# Surf5.net
KiCad netlist of a schematic drawn in Altium Designer
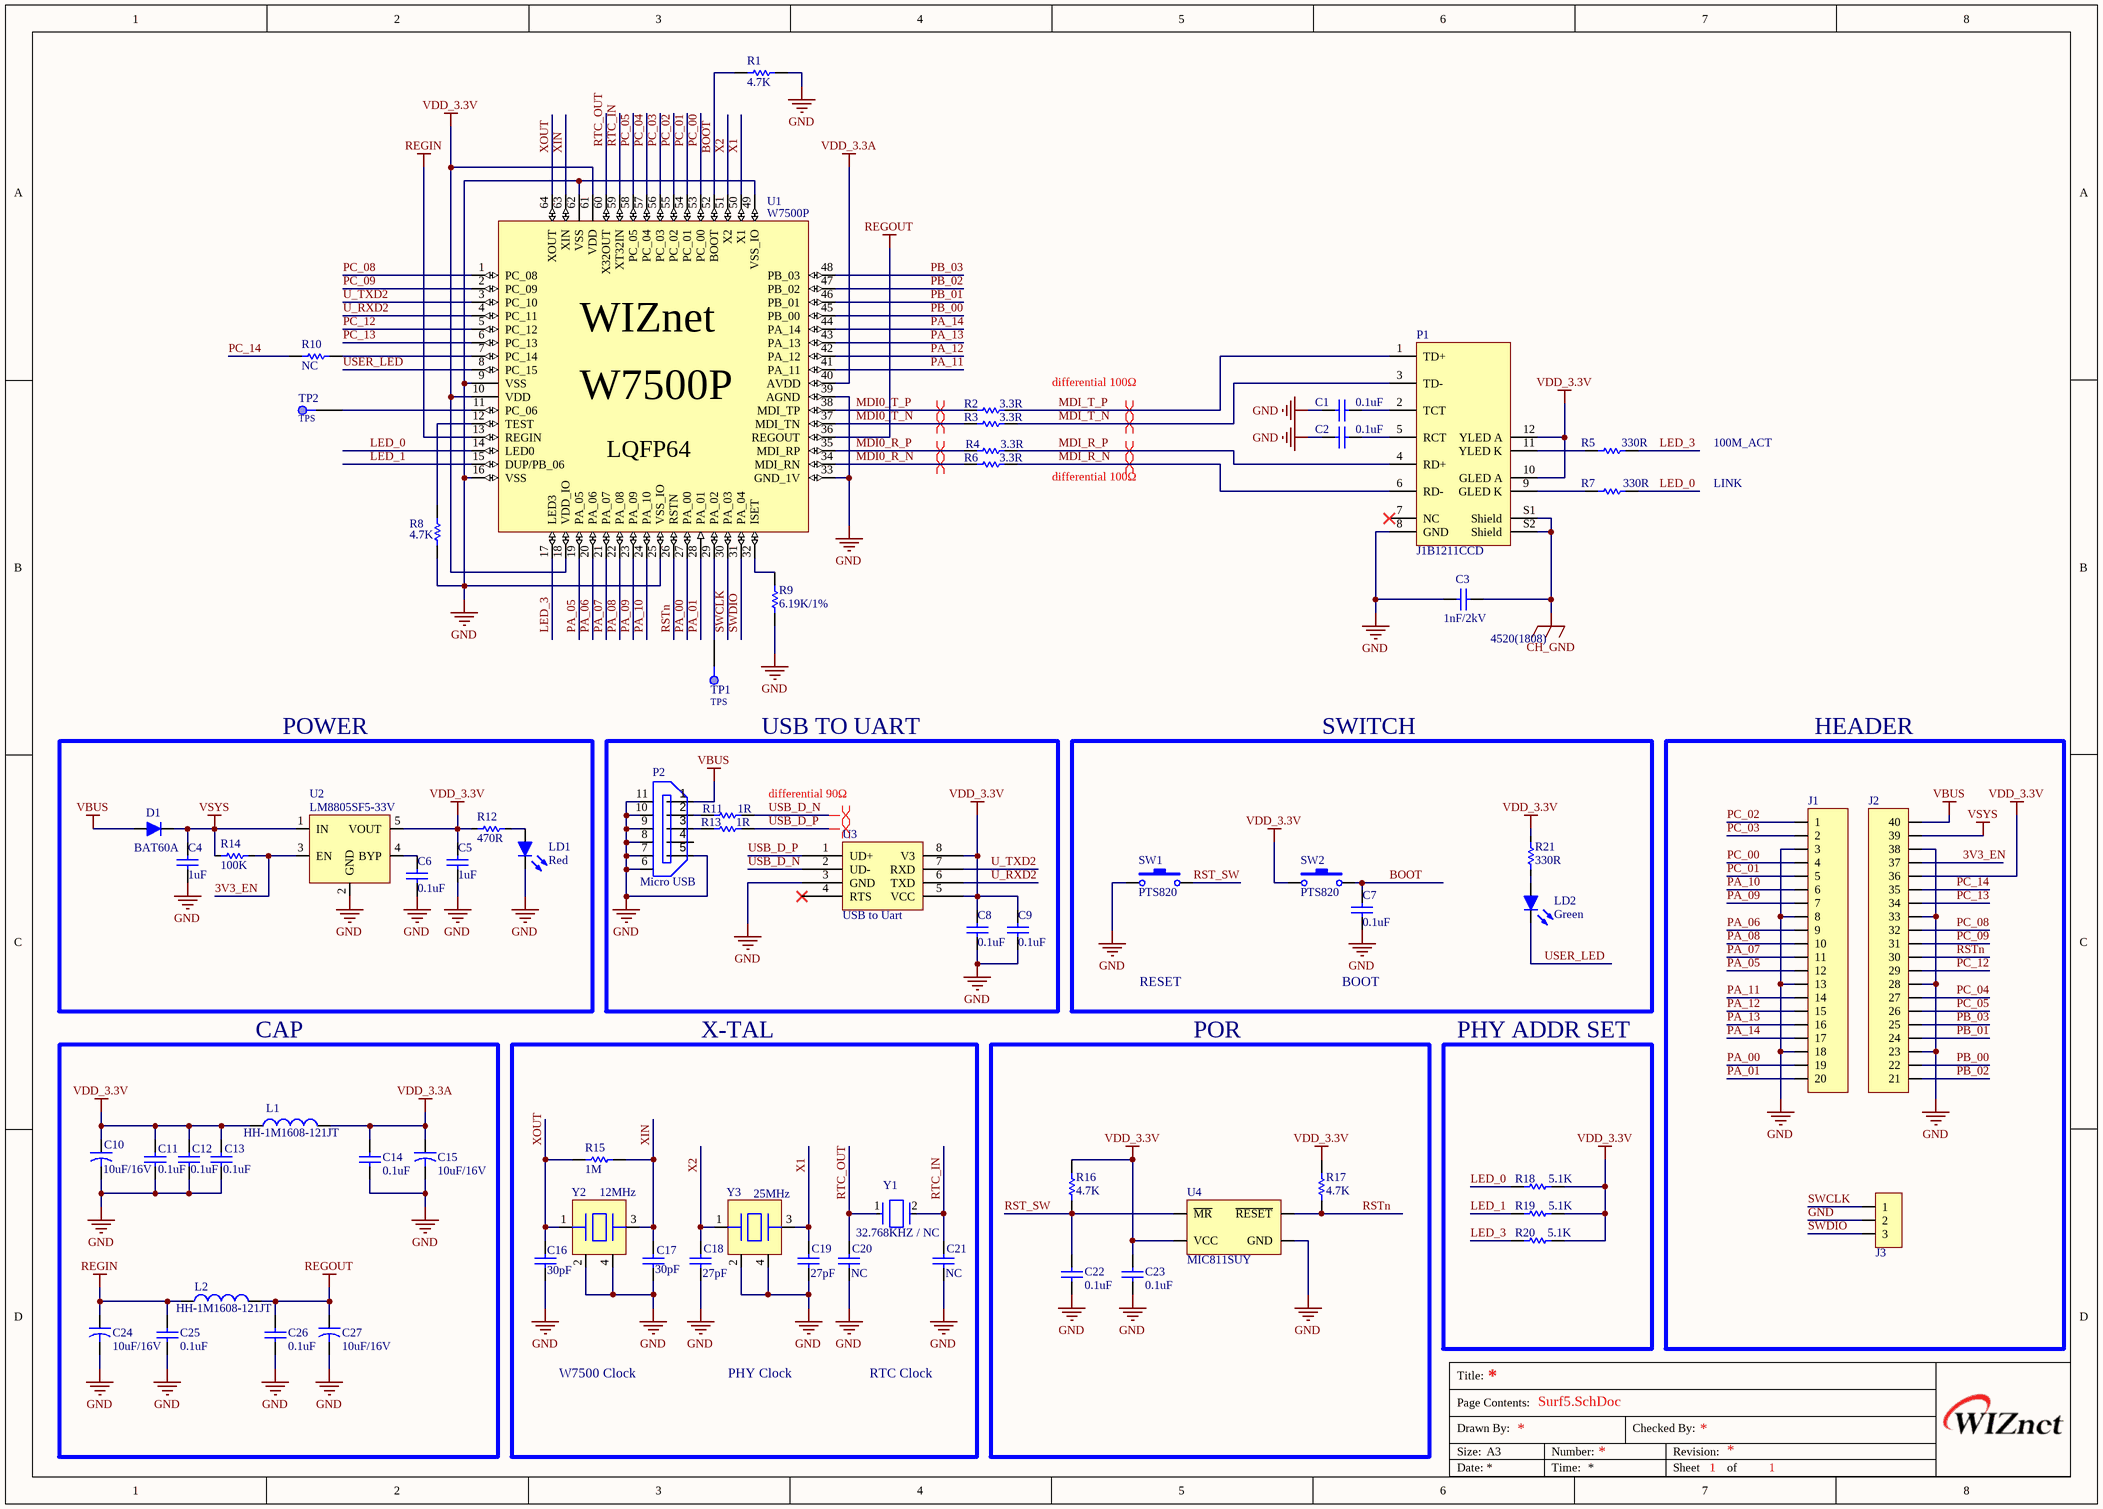
[diagram p0: Surf5.SchDoc]

(export (version "E")
  (design (tool "Eeschema 10.0.6"))
  (components
    (comp (ref "C1")
      (value "0.1uF")
      (footprint "CAP-0402")
      (description "Ceramic CAP 0402(1005)")
      (libsource (lib "Scott_lib") (part "CAP-0402"))
    )
    (comp (ref "C2")
      (value "0.1uF")
      (footprint "CAP-0402")
      (description "Ceramic CAP 0402(1005)")
      (libsource (lib "Scott_lib") (part "CAP-0402"))
    )
    (comp (ref "C3")
      (value "1nF/2kV")
      (footprint "CAP-1808")
      (description "Ceramic CAP 1808(4520)")
      (libsource (lib "Scott_lib") (part "CAP-1808"))
    )
    (comp (ref "C4")
      (value "1uF")
      (footprint "CAP-0402")
      (description "Ceramic CAP 0402(1005)")
      (libsource (lib "Scott_lib") (part "CAP-0402"))
    )
    (comp (ref "C5")
      (value "1uF")
      (footprint "CAP-0402")
      (description "Ceramic CAP 0402(1005)")
      (libsource (lib "Scott_lib") (part "CAP-0402"))
    )
    (comp (ref "C6")
      (value "0.1uF")
      (footprint "CAP-0402")
      (description "Ceramic CAP 0402(1005)")
      (libsource (lib "Scott_lib") (part "CAP-0402"))
    )
    (comp (ref "C7")
      (value "0.1uF")
      (footprint "CAP-0402")
      (description "Ceramic CAP 0402(1005)")
      (libsource (lib "Scott_lib") (part "CAP-0402"))
    )
    (comp (ref "C8")
      (value "0.1uF")
      (footprint "CAP-0402")
      (description "Ceramic CAP 0402(1005)")
      (libsource (lib "Scott_lib") (part "CAP-0402"))
    )
    (comp (ref "C9")
      (value "0.1uF")
      (footprint "CAP-0402")
      (description "Ceramic CAP 0402(1005)")
      (libsource (lib "Scott_lib") (part "CAP-0402"))
    )
    (comp (ref "C10")
      (value "10uF/16V")
      (footprint "CAP-A Size")
      (description "Tantla CAP A Size EIA/IECQ 3216")
      (libsource (lib "Scott_lib") (part "CAP-A Size"))
    )
    (comp (ref "C11")
      (value "0.1uF")
      (footprint "CAP-0402")
      (description "Ceramic CAP 0402(1005)")
      (libsource (lib "Scott_lib") (part "CAP-0402"))
    )
    (comp (ref "C12")
      (value "0.1uF")
      (footprint "CAP-0402")
      (description "Ceramic CAP 0402(1005)")
      (libsource (lib "Scott_lib") (part "CAP-0402"))
    )
    (comp (ref "C13")
      (value "0.1uF")
      (footprint "CAP-0402")
      (description "Ceramic CAP 0402(1005)")
      (libsource (lib "Scott_lib") (part "CAP-0402"))
    )
    (comp (ref "C14")
      (value "0.1uF")
      (footprint "CAP-0402")
      (description "Ceramic CAP 0402(1005)")
      (libsource (lib "Scott_lib") (part "CAP-0402"))
    )
    (comp (ref "C15")
      (value "10uF/16V")
      (footprint "CAP-A Size")
      (description "Tantla CAP A Size EIA/IECQ 3216")
      (libsource (lib "") (part "CAP-A Size_1"))
    )
    (comp (ref "C16")
      (value "30pF")
      (footprint "CAP-0402")
      (description "Ceramic CAP 0402(1005)")
      (libsource (lib "Scott_lib") (part "CAP-0402"))
    )
    (comp (ref "C17")
      (value "30pF")
      (footprint "CAP-0402")
      (description "Ceramic CAP 0402(1005)")
      (libsource (lib "Scott_lib") (part "CAP-0402"))
    )
    (comp (ref "C18")
      (value "27pF")
      (footprint "CAP-0402")
      (description "Ceramic CAP 0402(1005)")
      (libsource (lib "Scott_lib") (part "CAP-0402"))
    )
    (comp (ref "C19")
      (value "27pF")
      (footprint "CAP-0402")
      (description "Ceramic CAP 0402(1005)")
      (libsource (lib "Scott_lib") (part "CAP-0402"))
    )
    (comp (ref "C20")
      (value "NC")
      (footprint "CAP-0402")
      (description "Ceramic CAP 0402(1005)")
      (libsource (lib "Scott_lib") (part "CAP-0402"))
    )
    (comp (ref "C21")
      (value "NC")
      (footprint "CAP-0402")
      (description "Ceramic CAP 0402(1005)")
      (libsource (lib "Scott_lib") (part "CAP-0402"))
    )
    (comp (ref "C22")
      (value "0.1uF")
      (footprint "CAP-0402")
      (description "Ceramic CAP 0402(1005)")
      (libsource (lib "Scott_lib") (part "CAP-0402"))
    )
    (comp (ref "C23")
      (value "0.1uF")
      (footprint "CAP-0402")
      (description "Ceramic CAP 0402(1005)")
      (libsource (lib "Scott_lib") (part "CAP-0402"))
    )
    (comp (ref "C24")
      (value "10uF/16V")
      (footprint "CAP-A Size")
      (description "Tantla CAP A Size EIA/IECQ 3216")
      (libsource (lib "Scott_lib") (part "CAP-A Size"))
    )
    (comp (ref "C25")
      (value "0.1uF")
      (footprint "CAP-0402")
      (description "Ceramic CAP 0402(1005)")
      (libsource (lib "Scott_lib") (part "CAP-0402"))
    )
    (comp (ref "C26")
      (value "0.1uF")
      (footprint "CAP-0402")
      (description "Ceramic CAP 0402(1005)")
      (libsource (lib "Scott_lib") (part "CAP-0402"))
    )
    (comp (ref "C27")
      (value "10uF/16V")
      (footprint "CAP-A Size")
      (description "Tantla CAP A Size EIA/IECQ 3216")
      (libsource (lib "Scott_lib") (part "CAP-A Size"))
    )
    (comp (ref "D1")
      (value "BAT60A")
      (footprint "SOD-323(1-C,2-A)")
      (description "Silicon Schottky Diode")
      (libsource (lib "Scott_lib") (part "DIODE-BAT60A"))
    )
    (comp (ref "J1")
      (value "2.54mm 1x20 Pin Header DIP")
      (footprint "IDC-1X20")
      (libsource (lib "") (part "2.54mm 1x20 Pin Header DIP_1"))
    )
    (comp (ref "J2")
      (value "2.54mm 1x20 Pin Header DIP")
      (footprint "IDC-1X20")
      (libsource (lib "Scott_lib") (part "2.54mm 1x20 Pin Header DIP"))
    )
    (comp (ref "J3")
      (value "2.54mm 1x3 Pin Header DIP")
      (footprint "idc-1x3")
      (libsource (lib "Scott_lib") (part "2.54mm 1x3 Pin Header DIP"))
    )
    (comp (ref "L1")
      (value "HH-1M1608-121JT")
      (footprint "IND-0603")
      (description "Inductor 0603(1608)")
      (libsource (lib "Scott_lib") (part "IND-0603"))
    )
    (comp (ref "L2")
      (value "HH-1M1608-121JT")
      (footprint "IND-0603")
      (description "Inductor 0603(1608)")
      (libsource (lib "Scott_lib") (part "IND-0603"))
    )
    (comp (ref "LD1")
      (value "Red")
      (footprint "LED-0603-RED")
      (description "LED-0603")
      (libsource (lib "Scott_lib") (part "LED-0603"))
    )
    (comp (ref "LD2")
      (value "Green")
      (footprint "LED-0603-RED")
      (description "LED-0603")
      (libsource (lib "Scott_lib") (part "LED-0603"))
    )
    (comp (ref "P1")
      (value "J1B1211CCD")
      (footprint "Jaden_Lib:RJ45-J1B1211CCD")
      (libsource (lib "Jaden_Lib") (part "J1B1211CCD"))
    )
    (comp (ref "P2")
      (value "Micro USB")
      (footprint "Micro 5P B DBX 6.4")
      (description "Micro USB B Connector SMD")
      (libsource (lib "Scott_lib") (part "Micro USB 5P DBX6.4"))
    )
    (comp (ref "R1")
      (value "4.7K")
      (footprint "RES-0402")
      (description "RES-0402")
      (libsource (lib "Scott_lib") (part "RES-0402"))
    )
    (comp (ref "R2")
      (value "3.3R")
      (footprint "RES-0402")
      (description "RES-0402")
      (libsource (lib "Scott_lib") (part "RES-0402"))
    )
    (comp (ref "R3")
      (value "3.3R")
      (footprint "RES-0402")
      (description "RES-0402")
      (libsource (lib "Scott_lib") (part "RES-0402"))
    )
    (comp (ref "R4")
      (value "3.3R")
      (footprint "RES-0402")
      (description "RES-0402")
      (libsource (lib "Scott_lib") (part "RES-0402"))
    )
    (comp (ref "R5")
      (value "330R")
      (footprint "RES-0402")
      (description "RES-0402")
      (libsource (lib "Scott_lib") (part "RES-0402"))
    )
    (comp (ref "R6")
      (value "3.3R")
      (footprint "RES-0402")
      (description "RES-0402")
      (libsource (lib "Scott_lib") (part "RES-0402"))
    )
    (comp (ref "R7")
      (value "330R")
      (footprint "RES-0402")
      (description "RES-0402")
      (libsource (lib "Scott_lib") (part "RES-0402"))
    )
    (comp (ref "R8")
      (value "4.7K")
      (footprint "RES-0402")
      (description "RES-0402")
      (libsource (lib "Scott_lib") (part "RES-0402"))
    )
    (comp (ref "R9")
      (value "6.19K/1%")
      (footprint "RES-0402")
      (description "RES-0402")
      (libsource (lib "Scott_lib") (part "RES-0402"))
    )
    (comp (ref "R10")
      (value "NC")
      (footprint "RES-0402")
      (description "RES-0402")
      (libsource (lib "Scott_lib") (part "RES-0402"))
    )
    (comp (ref "R11")
      (value "1R")
      (footprint "RES-0402")
      (description "RES-0402")
      (libsource (lib "Scott_lib") (part "RES-0402"))
    )
    (comp (ref "R12")
      (value "470R")
      (footprint "RES-0402")
      (description "RES-0402")
      (libsource (lib "") (part "RES-0402_1"))
    )
    (comp (ref "R13")
      (value "1R")
      (footprint "RES-0402")
      (description "RES-0402")
      (libsource (lib "Scott_lib") (part "RES-0402"))
    )
    (comp (ref "R14")
      (value "100K")
      (footprint "RES-0402")
      (description "RES-0402")
      (libsource (lib "") (part "RES-0402_1"))
    )
    (comp (ref "R15")
      (value "1M")
      (footprint "RES-0402")
      (description "RES-0402")
      (libsource (lib "Scott_lib") (part "RES-0402"))
    )
    (comp (ref "R16")
      (value "4.7K")
      (footprint "RES-0402")
      (description "RES-0402")
      (libsource (lib "Scott_lib") (part "RES-0402"))
    )
    (comp (ref "R17")
      (value "4.7K")
      (footprint "RES-0402")
      (description "RES-0402")
      (libsource (lib "Scott_lib") (part "RES-0402"))
    )
    (comp (ref "R18")
      (value "5.1K")
      (footprint "RES-0402")
      (description "RES-0402")
      (libsource (lib "Scott_lib") (part "RES-0402"))
    )
    (comp (ref "R19")
      (value "5.1K")
      (footprint "RES-0402")
      (description "RES-0402")
      (libsource (lib "Scott_lib") (part "RES-0402"))
    )
    (comp (ref "R20")
      (value "5.1K")
      (footprint "RES-0402")
      (description "RES-0402")
      (libsource (lib "Scott_lib") (part "RES-0402"))
    )
    (comp (ref "R21")
      (value "330R")
      (footprint "RES-0402")
      (description "RES-0402")
      (libsource (lib "") (part "RES-0402_1"))
    )
    (comp (ref "SW1")
      (value "PTS820")
      (footprint "1185A")
      (description "TACT Switch (SMD)")
      (libsource (lib "Scott_lib") (part "ITS-1107(SMD)"))
    )
    (comp (ref "SW2")
      (value "PTS820")
      (footprint "1185A")
      (description "TACT Switch (SMD)")
      (libsource (lib "Scott_lib") (part "ITS-1107(SMD)"))
    )
    (comp (ref "TP1")
      (value "TPS")
      (footprint "Jaden_Lib:TPS")
      (description "Test_point")
      (fields
        (field (name "MANUFACTURER") "Wurth Elektronik")
        (field (name "PART NUMBER") "61300211121")
        (field (name "PUBLISHER") "WurthElektronik")
      )
      (libsource (lib "Jaden_Lib") (part "TPS"))
    )
    (comp (ref "TP2")
      (value "TPS")
      (footprint "Jaden_Lib:TPS")
      (description "Test_point")
      (fields
        (field (name "MANUFACTURER") "Wurth Elektronik")
        (field (name "PART NUMBER") "61300211121")
        (field (name "PUBLISHER") "WurthElektronik")
      )
      (libsource (lib "Jaden_Lib") (part "TPS"))
    )
    (comp (ref "U1")
      (value "W7500P")
      (footprint "W7500-LQFP64")
      (description "WIZnet ARM Cortex-M0, Add PHY")
      (libsource (lib "Scott_lib") (part "W7500P"))
    )
    (comp (ref "U2")
      (value "LM8805SF5-33V")
      (footprint "SOT-23-5L")
      (description "600mA CMOS LDO Regulator")
      (libsource (lib "Scott_lib") (part "LM8805SF5-33V"))
    )
    (comp (ref "U3") (value "USB to Uart") (footprint "CH340N") (libsource (lib "Jaden_Lib") (part "CH340N")))
    (comp (ref "U4")
      (value "MIC811SUY")
      (footprint "SOT-143")
      (description "Microprocessor Reset Circuits")
      (libsource (lib "Scott_lib") (part "MIC811SUY"))
    )
    (comp (ref "Y1")
      (value "32.768KHZ / NC")
      (footprint "3215_XTAL")
      (description "CRYSTAL 32.7680KHZ 6PF SMD")
      (fields (field (name "TOLERANCE") "20ppm"))
      (libsource (lib "Jaden_Lib") (part "XTAL 3215"))
    )
    (comp (ref "Y2")
      (value "12MHz")
      (footprint "OSC-TZ1067B")
      (description "X-tal 12MHz,3.2x2.5 SMD, CL=20pF")
      (libsource (lib "Scott_lib") (part "OSC-TZ1067B-12MHz"))
    )
    (comp (ref "Y3")
      (value "25MHz")
      (footprint "OSC-82J0626")
      (description "X-tal 25MHz,3.2x2.5 SMD, CL=18pF")
      (libsource (lib "Scott_lib") (part "OSC-82J0626-25MHz"))
    )
  )
  (nets
    (net (code "1") (name "/3V3_EN") (class "Default")
      (node (ref "J2") (pin "17") (pinfunction "37_17") (pintype "passive"))
      (node (ref "R14") (pin "2") (pinfunction "2_2") (pintype "passive"))
      (node (ref "U2") (pin "3") (pinfunction "EN_3") (pintype "power_in"))
    )
    (net (code "2") (name "/BOOT") (class "Default")
      (node (ref "C7") (pin "2") (pinfunction "2_2") (pintype "passive"))
      (node (ref "R1") (pin "2") (pinfunction "2_2") (pintype "passive"))
      (node (ref "SW2") (pin "2") (pinfunction "2_2") (pintype "passive"))
      (node (ref "U1") (pin "52") (pinfunction "BOOT_52") (pintype "bidirectional"))
    )
    (net (code "3") (name "/LED_0") (class "Default")
      (node (ref "R18") (pin "1") (pinfunction "1_1") (pintype "passive"))
      (node (ref "R7") (pin "2") (pinfunction "2_2") (pintype "passive"))
      (node (ref "U1") (pin "14") (pinfunction "LED0_14") (pintype "bidirectional"))
    )
    (net (code "4") (name "/LED_1") (class "Default")
      (node (ref "R19") (pin "1") (pinfunction "1_1") (pintype "passive"))
      (node (ref "U1") (pin "15") (pinfunction "DUP/PB_06_15") (pintype "bidirectional"))
    )
    (net (code "5") (name "/LED_3") (class "Default")
      (node (ref "R20") (pin "1") (pinfunction "1_1") (pintype "passive"))
      (node (ref "R5") (pin "2") (pinfunction "2_2") (pintype "passive"))
      (node (ref "U1") (pin "17") (pinfunction "LED3_17") (pintype "bidirectional"))
    )
    (net (code "6") (name "/MDI0_R_N") (class "Default")
      (node (ref "R6") (pin "1") (pinfunction "1_1") (pintype "passive"))
      (node (ref "U1") (pin "34") (pinfunction "MDI_RN_34") (pintype "bidirectional"))
    )
    (net (code "7") (name "/MDI0_R_P") (class "Default")
      (node (ref "R4") (pin "1") (pinfunction "1_1") (pintype "passive"))
      (node (ref "U1") (pin "35") (pinfunction "MDI_RP_35") (pintype "bidirectional"))
    )
    (net (code "8") (name "/MDI0_T_N") (class "Default")
      (node (ref "R3") (pin "1") (pinfunction "1_1") (pintype "passive"))
      (node (ref "U1") (pin "37") (pinfunction "MDI_TN_37") (pintype "bidirectional"))
    )
    (net (code "9") (name "/MDI0_T_P") (class "Default")
      (node (ref "R2") (pin "1") (pinfunction "1_1") (pintype "passive"))
      (node (ref "U1") (pin "38") (pinfunction "MDI_TP_38") (pintype "bidirectional"))
    )
    (net (code "10") (name "/MDI_R_N") (class "Default")
      (node (ref "P1") (pin "6") (pinfunction "RD-_6") (pintype "passive"))
      (node (ref "R6") (pin "2") (pinfunction "2_2") (pintype "passive"))
    )
    (net (code "11") (name "/MDI_R_P") (class "Default")
      (node (ref "P1") (pin "4") (pinfunction "RD+_4") (pintype "passive"))
      (node (ref "R4") (pin "2") (pinfunction "2_2") (pintype "passive"))
    )
    (net (code "12") (name "/MDI_T_N") (class "Default")
      (node (ref "P1") (pin "3") (pinfunction "TD-_3") (pintype "passive"))
      (node (ref "R3") (pin "2") (pinfunction "2_2") (pintype "passive"))
    )
    (net (code "13") (name "/MDI_T_P") (class "Default")
      (node (ref "P1") (pin "1") (pinfunction "TD+_1") (pintype "passive"))
      (node (ref "R2") (pin "2") (pinfunction "2_2") (pintype "passive"))
    )
    (net (code "14") (name "/PA_00") (class "Default")
      (node (ref "J1") (pin "19") (pinfunction "19_19") (pintype "passive"))
      (node (ref "U1") (pin "27") (pinfunction "PA_00_27") (pintype "bidirectional"))
    )
    (net (code "15") (name "/PA_01") (class "Default")
      (node (ref "J1") (pin "20") (pinfunction "20_20") (pintype "passive"))
      (node (ref "U1") (pin "28") (pinfunction "PA_01_28") (pintype "input"))
    )
    (net (code "16") (name "/PA_05") (class "Default")
      (node (ref "J1") (pin "12") (pinfunction "12_12") (pintype "passive"))
      (node (ref "U1") (pin "19") (pinfunction "PA_05_19") (pintype "bidirectional"))
    )
    (net (code "17") (name "/PA_06") (class "Default")
      (node (ref "J1") (pin "9") (pinfunction "9_9") (pintype "passive"))
      (node (ref "U1") (pin "20") (pinfunction "PA_06_20") (pintype "bidirectional"))
    )
    (net (code "18") (name "/PA_07") (class "Default")
      (node (ref "J1") (pin "11") (pinfunction "11_11") (pintype "passive"))
      (node (ref "U1") (pin "21") (pinfunction "PA_07_21") (pintype "bidirectional"))
    )
    (net (code "19") (name "/PA_08") (class "Default")
      (node (ref "J1") (pin "10") (pinfunction "10_10") (pintype "passive"))
      (node (ref "U1") (pin "22") (pinfunction "PA_08_22") (pintype "bidirectional"))
    )
    (net (code "20") (name "/PA_09") (class "Default")
      (node (ref "J1") (pin "7") (pinfunction "7_7") (pintype "passive"))
      (node (ref "U1") (pin "23") (pinfunction "PA_09_23") (pintype "bidirectional"))
    )
    (net (code "21") (name "/PA_10") (class "Default")
      (node (ref "J1") (pin "6") (pinfunction "6_6") (pintype "passive"))
      (node (ref "U1") (pin "24") (pinfunction "PA_10_24") (pintype "bidirectional"))
    )
    (net (code "22") (name "/PA_11") (class "Default")
      (node (ref "J1") (pin "14") (pinfunction "14_14") (pintype "passive"))
      (node (ref "U1") (pin "41") (pinfunction "PA_11_41") (pintype "bidirectional"))
    )
    (net (code "23") (name "/PA_12") (class "Default")
      (node (ref "J1") (pin "15") (pinfunction "15_15") (pintype "passive"))
      (node (ref "U1") (pin "42") (pinfunction "PA_12_42") (pintype "bidirectional"))
    )
    (net (code "24") (name "/PA_13") (class "Default")
      (node (ref "J1") (pin "16") (pinfunction "16_16") (pintype "passive"))
      (node (ref "U1") (pin "43") (pinfunction "PA_13_43") (pintype "bidirectional"))
    )
    (net (code "25") (name "/PA_14") (class "Default")
      (node (ref "J1") (pin "17") (pinfunction "17_17") (pintype "passive"))
      (node (ref "U1") (pin "44") (pinfunction "PA_14_44") (pintype "bidirectional"))
    )
    (net (code "26") (name "/PB_00") (class "Default")
      (node (ref "J2") (pin "2") (pinfunction "22_2") (pintype "passive"))
      (node (ref "U1") (pin "45") (pinfunction "PB_00_45") (pintype "bidirectional"))
    )
    (net (code "27") (name "/PB_01") (class "Default")
      (node (ref "J2") (pin "4") (pinfunction "24_4") (pintype "passive"))
      (node (ref "U1") (pin "46") (pinfunction "PB_01_46") (pintype "bidirectional"))
    )
    (net (code "28") (name "/PB_02") (class "Default")
      (node (ref "J2") (pin "1") (pinfunction "21_1") (pintype "passive"))
      (node (ref "U1") (pin "47") (pinfunction "PB_02_47") (pintype "bidirectional"))
    )
    (net (code "29") (name "/PB_03") (class "Default")
      (node (ref "J2") (pin "5") (pinfunction "25_5") (pintype "passive"))
      (node (ref "U1") (pin "48") (pinfunction "PB_03_48") (pintype "bidirectional"))
    )
    (net (code "30") (name "/PC_00") (class "Default")
      (node (ref "J1") (pin "4") (pinfunction "4_4") (pintype "passive"))
      (node (ref "U1") (pin "53") (pinfunction "PC_00_53") (pintype "bidirectional"))
    )
    (net (code "31") (name "/PC_01") (class "Default")
      (node (ref "J1") (pin "5") (pinfunction "5_5") (pintype "passive"))
      (node (ref "U1") (pin "54") (pinfunction "PC_01_54") (pintype "bidirectional"))
    )
    (net (code "32") (name "/PC_02") (class "Default")
      (node (ref "J1") (pin "1") (pinfunction "1_1") (pintype "passive"))
      (node (ref "U1") (pin "55") (pinfunction "PC_02_55") (pintype "bidirectional"))
    )
    (net (code "33") (name "/PC_03") (class "Default")
      (node (ref "J1") (pin "2") (pinfunction "2_2") (pintype "passive"))
      (node (ref "U1") (pin "56") (pinfunction "PC_03_56") (pintype "bidirectional"))
    )
    (net (code "34") (name "/PC_04") (class "Default")
      (node (ref "J2") (pin "7") (pinfunction "27_7") (pintype "passive"))
      (node (ref "U1") (pin "57") (pinfunction "PC_04_57") (pintype "bidirectional"))
    )
    (net (code "35") (name "/PC_05") (class "Default")
      (node (ref "J2") (pin "6") (pinfunction "26_6") (pintype "passive"))
      (node (ref "U1") (pin "58") (pinfunction "PC_05_58") (pintype "bidirectional"))
    )
    (net (code "36") (name "/PC_08") (class "Default")
      (node (ref "J2") (pin "12") (pinfunction "32_12") (pintype "passive"))
      (node (ref "U1") (pin "1") (pinfunction "PC_08_1") (pintype "bidirectional"))
    )
    (net (code "37") (name "/PC_09") (class "Default")
      (node (ref "J2") (pin "11") (pinfunction "31_11") (pintype "passive"))
      (node (ref "U1") (pin "2") (pinfunction "PC_09_2") (pintype "bidirectional"))
    )
    (net (code "38") (name "/PC_12") (class "Default")
      (node (ref "J2") (pin "9") (pinfunction "29_9") (pintype "passive"))
      (node (ref "U1") (pin "5") (pinfunction "PC_12_5") (pintype "bidirectional"))
    )
    (net (code "39") (name "/PC_13") (class "Default")
      (node (ref "J2") (pin "14") (pinfunction "34_14") (pintype "passive"))
      (node (ref "U1") (pin "6") (pinfunction "PC_13_6") (pintype "bidirectional"))
    )
    (net (code "40") (name "/PC_14") (class "Default")
      (node (ref "J2") (pin "15") (pinfunction "35_15") (pintype "passive"))
      (node (ref "R10") (pin "1") (pinfunction "1_1") (pintype "passive"))
    )
    (net (code "41") (name "/RST_SW") (class "Default")
      (node (ref "C22") (pin "1") (pinfunction "1_1") (pintype "passive"))
      (node (ref "R16") (pin "1") (pinfunction "1_1") (pintype "passive"))
      (node (ref "SW1") (pin "2") (pinfunction "2_2") (pintype "passive"))
      (node (ref "U4") (pin "3") (pinfunction "MR_3") (pintype "passive"))
    )
    (net (code "42") (name "/RSTn") (class "Default")
      (node (ref "J2") (pin "10") (pinfunction "30_10") (pintype "passive"))
      (node (ref "R17") (pin "2") (pinfunction "2_2") (pintype "passive"))
      (node (ref "U1") (pin "26") (pinfunction "RSTN_26") (pintype "bidirectional"))
      (node (ref "U4") (pin "2") (pinfunction "RESET_2") (pintype "passive"))
    )
    (net (code "43") (name "/RTC_IN") (class "Default")
      (node (ref "C21") (pin "2") (pinfunction "2_2") (pintype "passive"))
      (node (ref "U1") (pin "59") (pinfunction "XT32IN_59") (pintype "bidirectional"))
      (node (ref "Y1") (pin "2") (pinfunction "2_2") (pintype "passive"))
    )
    (net (code "44") (name "/RTC_OUT") (class "Default")
      (node (ref "C20") (pin "2") (pinfunction "2_2") (pintype "passive"))
      (node (ref "U1") (pin "60") (pinfunction "X32OUT_60") (pintype "bidirectional"))
      (node (ref "Y1") (pin "1") (pinfunction "1_1") (pintype "passive"))
    )
    (net (code "45") (name "/SWCLK") (class "Default")
      (node (ref "J3") (pin "1") (pinfunction "1_1") (pintype "passive"))
      (node (ref "U1") (pin "30") (pinfunction "PA_03_30") (pintype "bidirectional"))
    )
    (net (code "46") (name "/SWDIO") (class "Default")
      (node (ref "J3") (pin "3") (pinfunction "3_3") (pintype "passive"))
      (node (ref "U1") (pin "31") (pinfunction "PA_04_31") (pintype "bidirectional"))
    )
    (net (code "47") (name "/USB_D_N") (class "Default")
      (node (ref "R11") (pin "2") (pinfunction "2_2") (pintype "passive"))
      (node (ref "U3") (pin "2") (pinfunction "UD-_2") (pintype "passive"))
    )
    (net (code "48") (name "/USB_D_P") (class "Default")
      (node (ref "R13") (pin "2") (pinfunction "2_2") (pintype "passive"))
      (node (ref "U3") (pin "1") (pinfunction "UD+_1") (pintype "passive"))
    )
    (net (code "49") (name "/USER_LED") (class "Default")
      (node (ref "LD2") (pin "2") (pinfunction "K_2") (pintype "passive"))
      (node (ref "U1") (pin "8") (pinfunction "PC_15_8") (pintype "bidirectional"))
    )
    (net (code "50") (name "/U_RXD2") (class "Default")
      (node (ref "U1") (pin "4") (pinfunction "PC_11_4") (pintype "bidirectional"))
      (node (ref "U3") (pin "6") (pinfunction "TXD_6") (pintype "passive"))
    )
    (net (code "51") (name "/U_TXD2") (class "Default")
      (node (ref "U1") (pin "3") (pinfunction "PC_10_3") (pintype "bidirectional"))
      (node (ref "U3") (pin "7") (pinfunction "RXD_7") (pintype "passive"))
    )
    (net (code "52") (name "/X1") (class "Default")
      (node (ref "C19") (pin "2") (pinfunction "2_2") (pintype "passive"))
      (node (ref "U1") (pin "50") (pinfunction "X1_50") (pintype "bidirectional"))
      (node (ref "Y3") (pin "3") (pinfunction "3_3") (pintype "passive"))
    )
    (net (code "53") (name "/X2") (class "Default")
      (node (ref "C18") (pin "2") (pinfunction "2_2") (pintype "passive"))
      (node (ref "U1") (pin "51") (pinfunction "X2_51") (pintype "bidirectional"))
      (node (ref "Y3") (pin "1") (pinfunction "1_1") (pintype "passive"))
    )
    (net (code "54") (name "/XIN") (class "Default")
      (node (ref "C17") (pin "2") (pinfunction "2_2") (pintype "passive"))
      (node (ref "R15") (pin "2") (pinfunction "2_2") (pintype "passive"))
      (node (ref "U1") (pin "63") (pinfunction "XIN_63") (pintype "bidirectional"))
      (node (ref "Y2") (pin "3") (pinfunction "3_3") (pintype "passive"))
    )
    (net (code "55") (name "/XOUT") (class "Default")
      (node (ref "C16") (pin "2") (pinfunction "2_2") (pintype "passive"))
      (node (ref "R15") (pin "1") (pinfunction "1_1") (pintype "passive"))
      (node (ref "U1") (pin "64") (pinfunction "XOUT_64") (pintype "bidirectional"))
      (node (ref "Y2") (pin "1") (pinfunction "1_1") (pintype "passive"))
    )
    (net (code "56") (name "CH_GND") (class "Default")
      (node (ref "C3") (pin "2") (pinfunction "2_2") (pintype "passive"))
      (node (ref "P1") (pin "S1") (pinfunction "Shield_S1") (pintype "passive"))
      (node (ref "P1") (pin "S2") (pinfunction "Shield_S2") (pintype "passive"))
    )
    (net (code "57") (name "GND") (class "Default")
      (node (ref "C1") (pin "1") (pinfunction "1_1") (pintype "passive"))
      (node (ref "C10") (pin "2") (pinfunction "2_2") (pintype "passive"))
      (node (ref "C11") (pin "1") (pinfunction "1_1") (pintype "passive"))
      (node (ref "C12") (pin "1") (pinfunction "1_1") (pintype "passive"))
      (node (ref "C13") (pin "1") (pinfunction "1_1") (pintype "passive"))
      (node (ref "C14") (pin "1") (pinfunction "1_1") (pintype "passive"))
      (node (ref "C15") (pin "2") (pinfunction "2_2") (pintype "passive"))
      (node (ref "C16") (pin "1") (pinfunction "1_1") (pintype "passive"))
      (node (ref "C17") (pin "1") (pinfunction "1_1") (pintype "passive"))
      (node (ref "C18") (pin "1") (pinfunction "1_1") (pintype "passive"))
      (node (ref "C19") (pin "1") (pinfunction "1_1") (pintype "passive"))
      (node (ref "C2") (pin "1") (pinfunction "1_1") (pintype "passive"))
      (node (ref "C20") (pin "1") (pinfunction "1_1") (pintype "passive"))
      (node (ref "C21") (pin "1") (pinfunction "1_1") (pintype "passive"))
      (node (ref "C22") (pin "2") (pinfunction "2_2") (pintype "passive"))
      (node (ref "C23") (pin "2") (pinfunction "2_2") (pintype "passive"))
      (node (ref "C24") (pin "2") (pinfunction "2_2") (pintype "passive"))
      (node (ref "C25") (pin "1") (pinfunction "1_1") (pintype "passive"))
      (node (ref "C26") (pin "1") (pinfunction "1_1") (pintype "passive"))
      (node (ref "C27") (pin "2") (pinfunction "2_2") (pintype "passive"))
      (node (ref "C3") (pin "1") (pinfunction "1_1") (pintype "passive"))
      (node (ref "C4") (pin "1") (pinfunction "1_1") (pintype "passive"))
      (node (ref "C5") (pin "1") (pinfunction "1_1") (pintype "passive"))
      (node (ref "C6") (pin "1") (pinfunction "1_1") (pintype "passive"))
      (node (ref "C7") (pin "1") (pinfunction "1_1") (pintype "passive"))
      (node (ref "C8") (pin "1") (pinfunction "1_1") (pintype "passive"))
      (node (ref "C9") (pin "1") (pinfunction "1_1") (pintype "passive"))
      (node (ref "J1") (pin "13") (pinfunction "13_13") (pintype "passive"))
      (node (ref "J1") (pin "18") (pinfunction "18_18") (pintype "passive"))
      (node (ref "J1") (pin "3") (pinfunction "3_3") (pintype "passive"))
      (node (ref "J1") (pin "8") (pinfunction "8_8") (pintype "passive"))
      (node (ref "J2") (pin "13") (pinfunction "33_13") (pintype "passive"))
      (node (ref "J2") (pin "18") (pinfunction "38_18") (pintype "passive"))
      (node (ref "J2") (pin "3") (pinfunction "23_3") (pintype "passive"))
      (node (ref "J2") (pin "8") (pinfunction "28_8") (pintype "passive"))
      (node (ref "J3") (pin "2") (pinfunction "2_2") (pintype "passive"))
      (node (ref "LD1") (pin "2") (pinfunction "K_2") (pintype "passive"))
      (node (ref "P1") (pin "8") (pinfunction "GND_8") (pintype "passive"))
      (node (ref "P2") (pin "10") (pinfunction "10_10") (pintype "passive"))
      (node (ref "P2") (pin "11") (pinfunction "11_11") (pintype "passive"))
      (node (ref "P2") (pin "5") (pinfunction "5_5") (pintype "passive"))
      (node (ref "P2") (pin "6") (pinfunction "6_6") (pintype "passive"))
      (node (ref "P2") (pin "7") (pinfunction "7_7") (pintype "passive"))
      (node (ref "P2") (pin "8") (pinfunction "8_8") (pintype "passive"))
      (node (ref "P2") (pin "9") (pinfunction "9_9") (pintype "passive"))
      (node (ref "R1") (pin "1") (pinfunction "1_1") (pintype "passive"))
      (node (ref "R8") (pin "1") (pinfunction "1_1") (pintype "passive"))
      (node (ref "R9") (pin "1") (pinfunction "1_1") (pintype "passive"))
      (node (ref "SW1") (pin "1") (pinfunction "1_1") (pintype "passive"))
      (node (ref "U1") (pin "16") (pinfunction "VSS_16") (pintype "bidirectional"))
      (node (ref "U1") (pin "25") (pinfunction "VSS_IO_25") (pintype "bidirectional"))
      (node (ref "U1") (pin "33") (pinfunction "GND_1V_33") (pintype "bidirectional"))
      (node (ref "U1") (pin "39") (pinfunction "AGND_39") (pintype "bidirectional"))
      (node (ref "U1") (pin "49") (pinfunction "VSS_IO_49") (pintype "bidirectional"))
      (node (ref "U1") (pin "62") (pinfunction "VSS_62") (pintype "power_in"))
      (node (ref "U1") (pin "9") (pinfunction "VSS_9") (pintype "power_in"))
      (node (ref "U2") (pin "2") (pinfunction "GND_2") (pintype "power_in"))
      (node (ref "U3") (pin "3") (pinfunction "GND_3") (pintype "passive"))
      (node (ref "U4") (pin "1") (pinfunction "GND_1") (pintype "passive"))
      (node (ref "Y2") (pin "2") (pinfunction "2_2") (pintype "passive"))
      (node (ref "Y2") (pin "4") (pinfunction "4_4") (pintype "passive"))
      (node (ref "Y3") (pin "2") (pinfunction "2_2") (pintype "passive"))
      (node (ref "Y3") (pin "4") (pinfunction "4_4") (pintype "passive"))
    )
    (net (code "58") (name "Net-(LD1-A)") (class "Default")
      (node (ref "LD1") (pin "1") (pinfunction "A_1") (pintype "passive"))
      (node (ref "R12") (pin "2") (pinfunction "2_2") (pintype "passive"))
    )
    (net (code "59") (name "Net-(LD2-A)") (class "Default")
      (node (ref "LD2") (pin "1") (pinfunction "A_1") (pintype "passive"))
      (node (ref "R21") (pin "1") (pinfunction "1_1") (pintype "passive"))
    )
    (net (code "60") (name "Net-(P1-GLED_K)") (class "Default")
      (node (ref "P1") (pin "9") (pinfunction "GLED_K_9") (pintype "passive"))
      (node (ref "R7") (pin "1") (pinfunction "1_1") (pintype "passive"))
    )
    (net (code "61") (name "Net-(P1-RCT)") (class "Default")
      (node (ref "C2") (pin "2") (pinfunction "2_2") (pintype "passive"))
      (node (ref "P1") (pin "5") (pinfunction "RCT_5") (pintype "passive"))
    )
    (net (code "62") (name "Net-(P1-TCT)") (class "Default")
      (node (ref "C1") (pin "2") (pinfunction "2_2") (pintype "passive"))
      (node (ref "P1") (pin "2") (pinfunction "TCT_2") (pintype "passive"))
    )
    (net (code "63") (name "Net-(P1-YLED_K)") (class "Default")
      (node (ref "P1") (pin "11") (pinfunction "YLED_K_11") (pintype "passive"))
      (node (ref "R5") (pin "1") (pinfunction "1_1") (pintype "passive"))
    )
    (net (code "64") (name "Net-(P2-Pad2)") (class "Default")
      (node (ref "P2") (pin "2") (pinfunction "2_2") (pintype "passive"))
      (node (ref "R11") (pin "1") (pinfunction "1_1") (pintype "passive"))
    )
    (net (code "65") (name "Net-(P2-Pad3)") (class "Default")
      (node (ref "P2") (pin "3") (pinfunction "3_3") (pintype "passive"))
      (node (ref "R13") (pin "1") (pinfunction "1_1") (pintype "passive"))
    )
    (net (code "66") (name "Net-(U1-ISET)") (class "Default")
      (node (ref "R9") (pin "2") (pinfunction "2_2") (pintype "passive"))
      (node (ref "U1") (pin "32") (pinfunction "ISET_32") (pintype "bidirectional"))
    )
    (net (code "67") (name "Net-(U1-PA_02)") (class "Default")
      (node (ref "TP1") (pin "1") (pinfunction "1_1") (pintype "passive"))
      (node (ref "U1") (pin "29") (pinfunction "PA_02_29") (pintype "bidirectional"))
    )
    (net (code "68") (name "Net-(U1-PC_06)") (class "Default")
      (node (ref "TP2") (pin "1") (pinfunction "1_1") (pintype "passive"))
      (node (ref "U1") (pin "11") (pinfunction "PC_06_11") (pintype "bidirectional"))
    )
    (net (code "69") (name "Net-(U1-PC_14)") (class "Default")
      (node (ref "R10") (pin "2") (pinfunction "2_2") (pintype "passive"))
      (node (ref "U1") (pin "7") (pinfunction "PC_14_7") (pintype "bidirectional"))
    )
    (net (code "70") (name "Net-(U1-TEST)") (class "Default")
      (node (ref "R8") (pin "2") (pinfunction "2_2") (pintype "passive"))
      (node (ref "U1") (pin "12") (pinfunction "TEST_12") (pintype "bidirectional"))
    )
    (net (code "71") (name "Net-(U2-BYP)") (class "Default")
      (node (ref "C6") (pin "2") (pinfunction "2_2") (pintype "passive"))
      (node (ref "U2") (pin "4") (pinfunction "BYP_4") (pintype "power_in"))
    )
    (net (code "72") (name "REGIN") (class "Default")
      (node (ref "C24") (pin "1") (pinfunction "1_1") (pintype "passive"))
      (node (ref "C25") (pin "2") (pinfunction "2_2") (pintype "passive"))
      (node (ref "L2") (pin "1") (pinfunction "1_1") (pintype "passive"))
      (node (ref "U1") (pin "13") (pinfunction "REGIN_13") (pintype "bidirectional"))
    )
    (net (code "73") (name "REGOUT") (class "Default")
      (node (ref "C26") (pin "2") (pinfunction "2_2") (pintype "passive"))
      (node (ref "C27") (pin "1") (pinfunction "1_1") (pintype "passive"))
      (node (ref "L2") (pin "2") (pinfunction "2_2") (pintype "passive"))
      (node (ref "U1") (pin "36") (pinfunction "REGOUT_36") (pintype "bidirectional"))
    )
    (net (code "74") (name "VBUS") (class "Default")
      (node (ref "D1") (pin "2") (pinfunction "A_2") (pintype "passive"))
      (node (ref "J2") (pin "20") (pinfunction "40_20") (pintype "passive"))
      (node (ref "P2") (pin "1") (pinfunction "1_1") (pintype "passive"))
    )
    (net (code "75") (name "VDD_3.3A") (class "Default")
      (node (ref "C14") (pin "2") (pinfunction "2_2") (pintype "passive"))
      (node (ref "C15") (pin "1") (pinfunction "1_1") (pintype "passive"))
      (node (ref "L1") (pin "2") (pinfunction "2_2") (pintype "passive"))
      (node (ref "U1") (pin "40") (pinfunction "AVDD_40") (pintype "bidirectional"))
    )
    (net (code "76") (name "VDD_3.3V") (class "Default")
      (node (ref "C10") (pin "1") (pinfunction "1_1") (pintype "passive"))
      (node (ref "C11") (pin "2") (pinfunction "2_2") (pintype "passive"))
      (node (ref "C12") (pin "2") (pinfunction "2_2") (pintype "passive"))
      (node (ref "C13") (pin "2") (pinfunction "2_2") (pintype "passive"))
      (node (ref "C23") (pin "1") (pinfunction "1_1") (pintype "passive"))
      (node (ref "C5") (pin "2") (pinfunction "2_2") (pintype "passive"))
      (node (ref "C8") (pin "2") (pinfunction "2_2") (pintype "passive"))
      (node (ref "C9") (pin "2") (pinfunction "2_2") (pintype "passive"))
      (node (ref "J2") (pin "16") (pinfunction "36_16") (pintype "passive"))
      (node (ref "L1") (pin "1") (pinfunction "1_1") (pintype "passive"))
      (node (ref "P1") (pin "10") (pinfunction "GLED_A_10") (pintype "passive"))
      (node (ref "P1") (pin "12") (pinfunction "YLED_A_12") (pintype "passive"))
      (node (ref "R12") (pin "1") (pinfunction "1_1") (pintype "passive"))
      (node (ref "R16") (pin "2") (pinfunction "2_2") (pintype "passive"))
      (node (ref "R17") (pin "1") (pinfunction "1_1") (pintype "passive"))
      (node (ref "R18") (pin "2") (pinfunction "2_2") (pintype "passive"))
      (node (ref "R19") (pin "2") (pinfunction "2_2") (pintype "passive"))
      (node (ref "R20") (pin "2") (pinfunction "2_2") (pintype "passive"))
      (node (ref "R21") (pin "2") (pinfunction "2_2") (pintype "passive"))
      (node (ref "SW2") (pin "1") (pinfunction "1_1") (pintype "passive"))
      (node (ref "U1") (pin "10") (pinfunction "VDD_10") (pintype "power_in"))
      (node (ref "U1") (pin "18") (pinfunction "VDD_IO_18") (pintype "bidirectional"))
      (node (ref "U1") (pin "61") (pinfunction "VDD_61") (pintype "power_in"))
      (node (ref "U2") (pin "5") (pinfunction "VOUT_5") (pintype "power_in"))
      (node (ref "U3") (pin "5") (pinfunction "VCC_5") (pintype "passive"))
      (node (ref "U3") (pin "8") (pinfunction "V3_8") (pintype "passive"))
      (node (ref "U4") (pin "4") (pinfunction "VCC_4") (pintype "passive"))
    )
    (net (code "77") (name "VSYS") (class "Default")
      (node (ref "C4") (pin "2") (pinfunction "2_2") (pintype "passive"))
      (node (ref "D1") (pin "1") (pinfunction "K_1") (pintype "passive"))
      (node (ref "J2") (pin "19") (pinfunction "39_19") (pintype "passive"))
      (node (ref "R14") (pin "1") (pinfunction "1_1") (pintype "passive"))
      (node (ref "U2") (pin "1") (pinfunction "IN_1") (pintype "power_in"))
    )
    (net (code "78") (name "unconnected-(P1-NC-Pad7)") (class "Default")
      (node (ref "P1") (pin "7") (pinfunction "NC_7") (pintype "passive+no_connect"))
    )
    (net (code "79") (name "unconnected-(P2-Pad4)") (class "Default")
      (node (ref "P2") (pin "4") (pinfunction "4_4") (pintype "passive"))
    )
    (net (code "80") (name "unconnected-(U3-RTS-Pad4)") (class "Default")
      (node (ref "U3") (pin "4") (pinfunction "RTS_4") (pintype "passive+no_connect"))
    )
  )
)
